# ConnectorInterface.net
KiCad netlist of a schematic drawn in Altium Designer
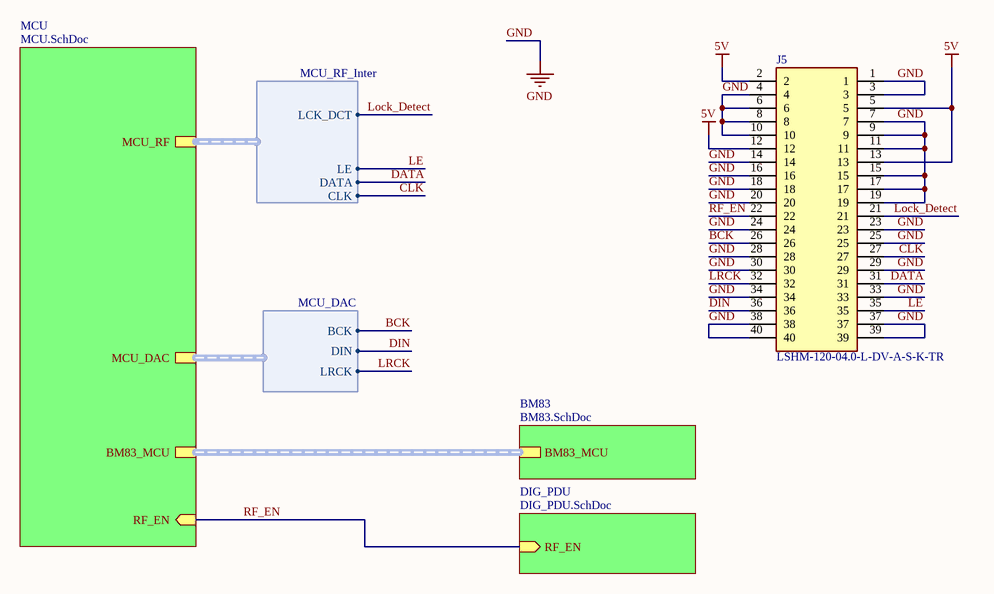
[diagram p0: ConnectorInterface.SchDoc]

(export (version "E")
  (design (tool "Eeschema 10.0.6"))
  (components
    (comp (ref "J5")
      (value "LSHM-120-04.0-L-DV-A-S-K-TR")
      (footprint "SamacSys:LSHM-120-XX.X-YYY-DV-A-S-K-TR")
      (description "Connector")
      (fields (field (name "MOUSER PART NUMBER") "200-LSHM12004LDVASK"))
      (libsource (lib "*") (part "LSHM-120-04.0-L-DV-A-S-K-TR"))
    )
  )
  (nets
    (net (code "3") (name "/BCK") (class "Default")
      (node (ref "J5") (pin "26") (pinfunction "26_26") (pintype "passive"))
    )
    (net (code "5") (name "/CLK") (class "Default")
      (node (ref "J5") (pin "27") (pinfunction "27_27") (pintype "passive"))
    )
    (net (code "6") (name "/DATA") (class "Default")
      (node (ref "J5") (pin "31") (pinfunction "31_31") (pintype "passive"))
    )
    (net (code "7") (name "/DIN") (class "Default")
      (node (ref "J5") (pin "36") (pinfunction "36_36") (pintype "passive"))
    )
    (net (code "8") (name "/LE") (class "Default")
      (node (ref "J5") (pin "35") (pinfunction "35_35") (pintype "passive"))
    )
    (net (code "9") (name "/LRCK") (class "Default")
      (node (ref "J5") (pin "32") (pinfunction "32_32") (pintype "passive"))
    )
    (net (code "10") (name "/Lock_Detect") (class "Default")
      (node (ref "J5") (pin "21") (pinfunction "21_21") (pintype "passive"))
    )
    (net (code "11") (name "/RF_EN") (class "Default")
      (node (ref "J5") (pin "22") (pinfunction "22_22") (pintype "passive"))
    )
    (net (code "14") (name "5V") (class "Default")
      (node (ref "J5") (pin "12") (pinfunction "12_12") (pintype "passive"))
      (node (ref "J5") (pin "13") (pinfunction "13_13") (pintype "passive"))
      (node (ref "J5") (pin "2") (pinfunction "2_2") (pintype "passive"))
      (node (ref "J5") (pin "5") (pinfunction "5_5") (pintype "passive"))
    )
    (net (code "15") (name "GND") (class "Default")
      (node (ref "J5") (pin "1") (pinfunction "1_1") (pintype "passive"))
      (node (ref "J5") (pin "10") (pinfunction "10_10") (pintype "passive"))
      (node (ref "J5") (pin "11") (pinfunction "11_11") (pintype "passive"))
      (node (ref "J5") (pin "14") (pinfunction "14_14") (pintype "passive"))
      (node (ref "J5") (pin "15") (pinfunction "15_15") (pintype "passive"))
      (node (ref "J5") (pin "16") (pinfunction "16_16") (pintype "passive"))
      (node (ref "J5") (pin "17") (pinfunction "17_17") (pintype "passive"))
      (node (ref "J5") (pin "18") (pinfunction "18_18") (pintype "passive"))
      (node (ref "J5") (pin "19") (pinfunction "19_19") (pintype "passive"))
      (node (ref "J5") (pin "20") (pinfunction "20_20") (pintype "passive"))
      (node (ref "J5") (pin "23") (pinfunction "23_23") (pintype "passive"))
      (node (ref "J5") (pin "24") (pinfunction "24_24") (pintype "passive"))
      (node (ref "J5") (pin "25") (pinfunction "25_25") (pintype "passive"))
      (node (ref "J5") (pin "28") (pinfunction "28_28") (pintype "passive"))
      (node (ref "J5") (pin "29") (pinfunction "29_29") (pintype "passive"))
      (node (ref "J5") (pin "3") (pinfunction "3_3") (pintype "passive"))
      (node (ref "J5") (pin "30") (pinfunction "30_30") (pintype "passive"))
      (node (ref "J5") (pin "33") (pinfunction "33_33") (pintype "passive"))
      (node (ref "J5") (pin "34") (pinfunction "34_34") (pintype "passive"))
      (node (ref "J5") (pin "37") (pinfunction "37_37") (pintype "passive"))
      (node (ref "J5") (pin "38") (pinfunction "38_38") (pintype "passive"))
      (node (ref "J5") (pin "39") (pinfunction "39_39") (pintype "passive"))
      (node (ref "J5") (pin "4") (pinfunction "4_4") (pintype "passive"))
      (node (ref "J5") (pin "40") (pinfunction "40_40") (pintype "passive"))
      (node (ref "J5") (pin "6") (pinfunction "6_6") (pintype "passive"))
      (node (ref "J5") (pin "7") (pinfunction "7_7") (pintype "passive"))
      (node (ref "J5") (pin "8") (pinfunction "8_8") (pintype "passive"))
      (node (ref "J5") (pin "9") (pinfunction "9_9") (pintype "passive"))
    )
  )
)
